# output_stage.net
KiCad netlist of a schematic drawn in Altium Designer
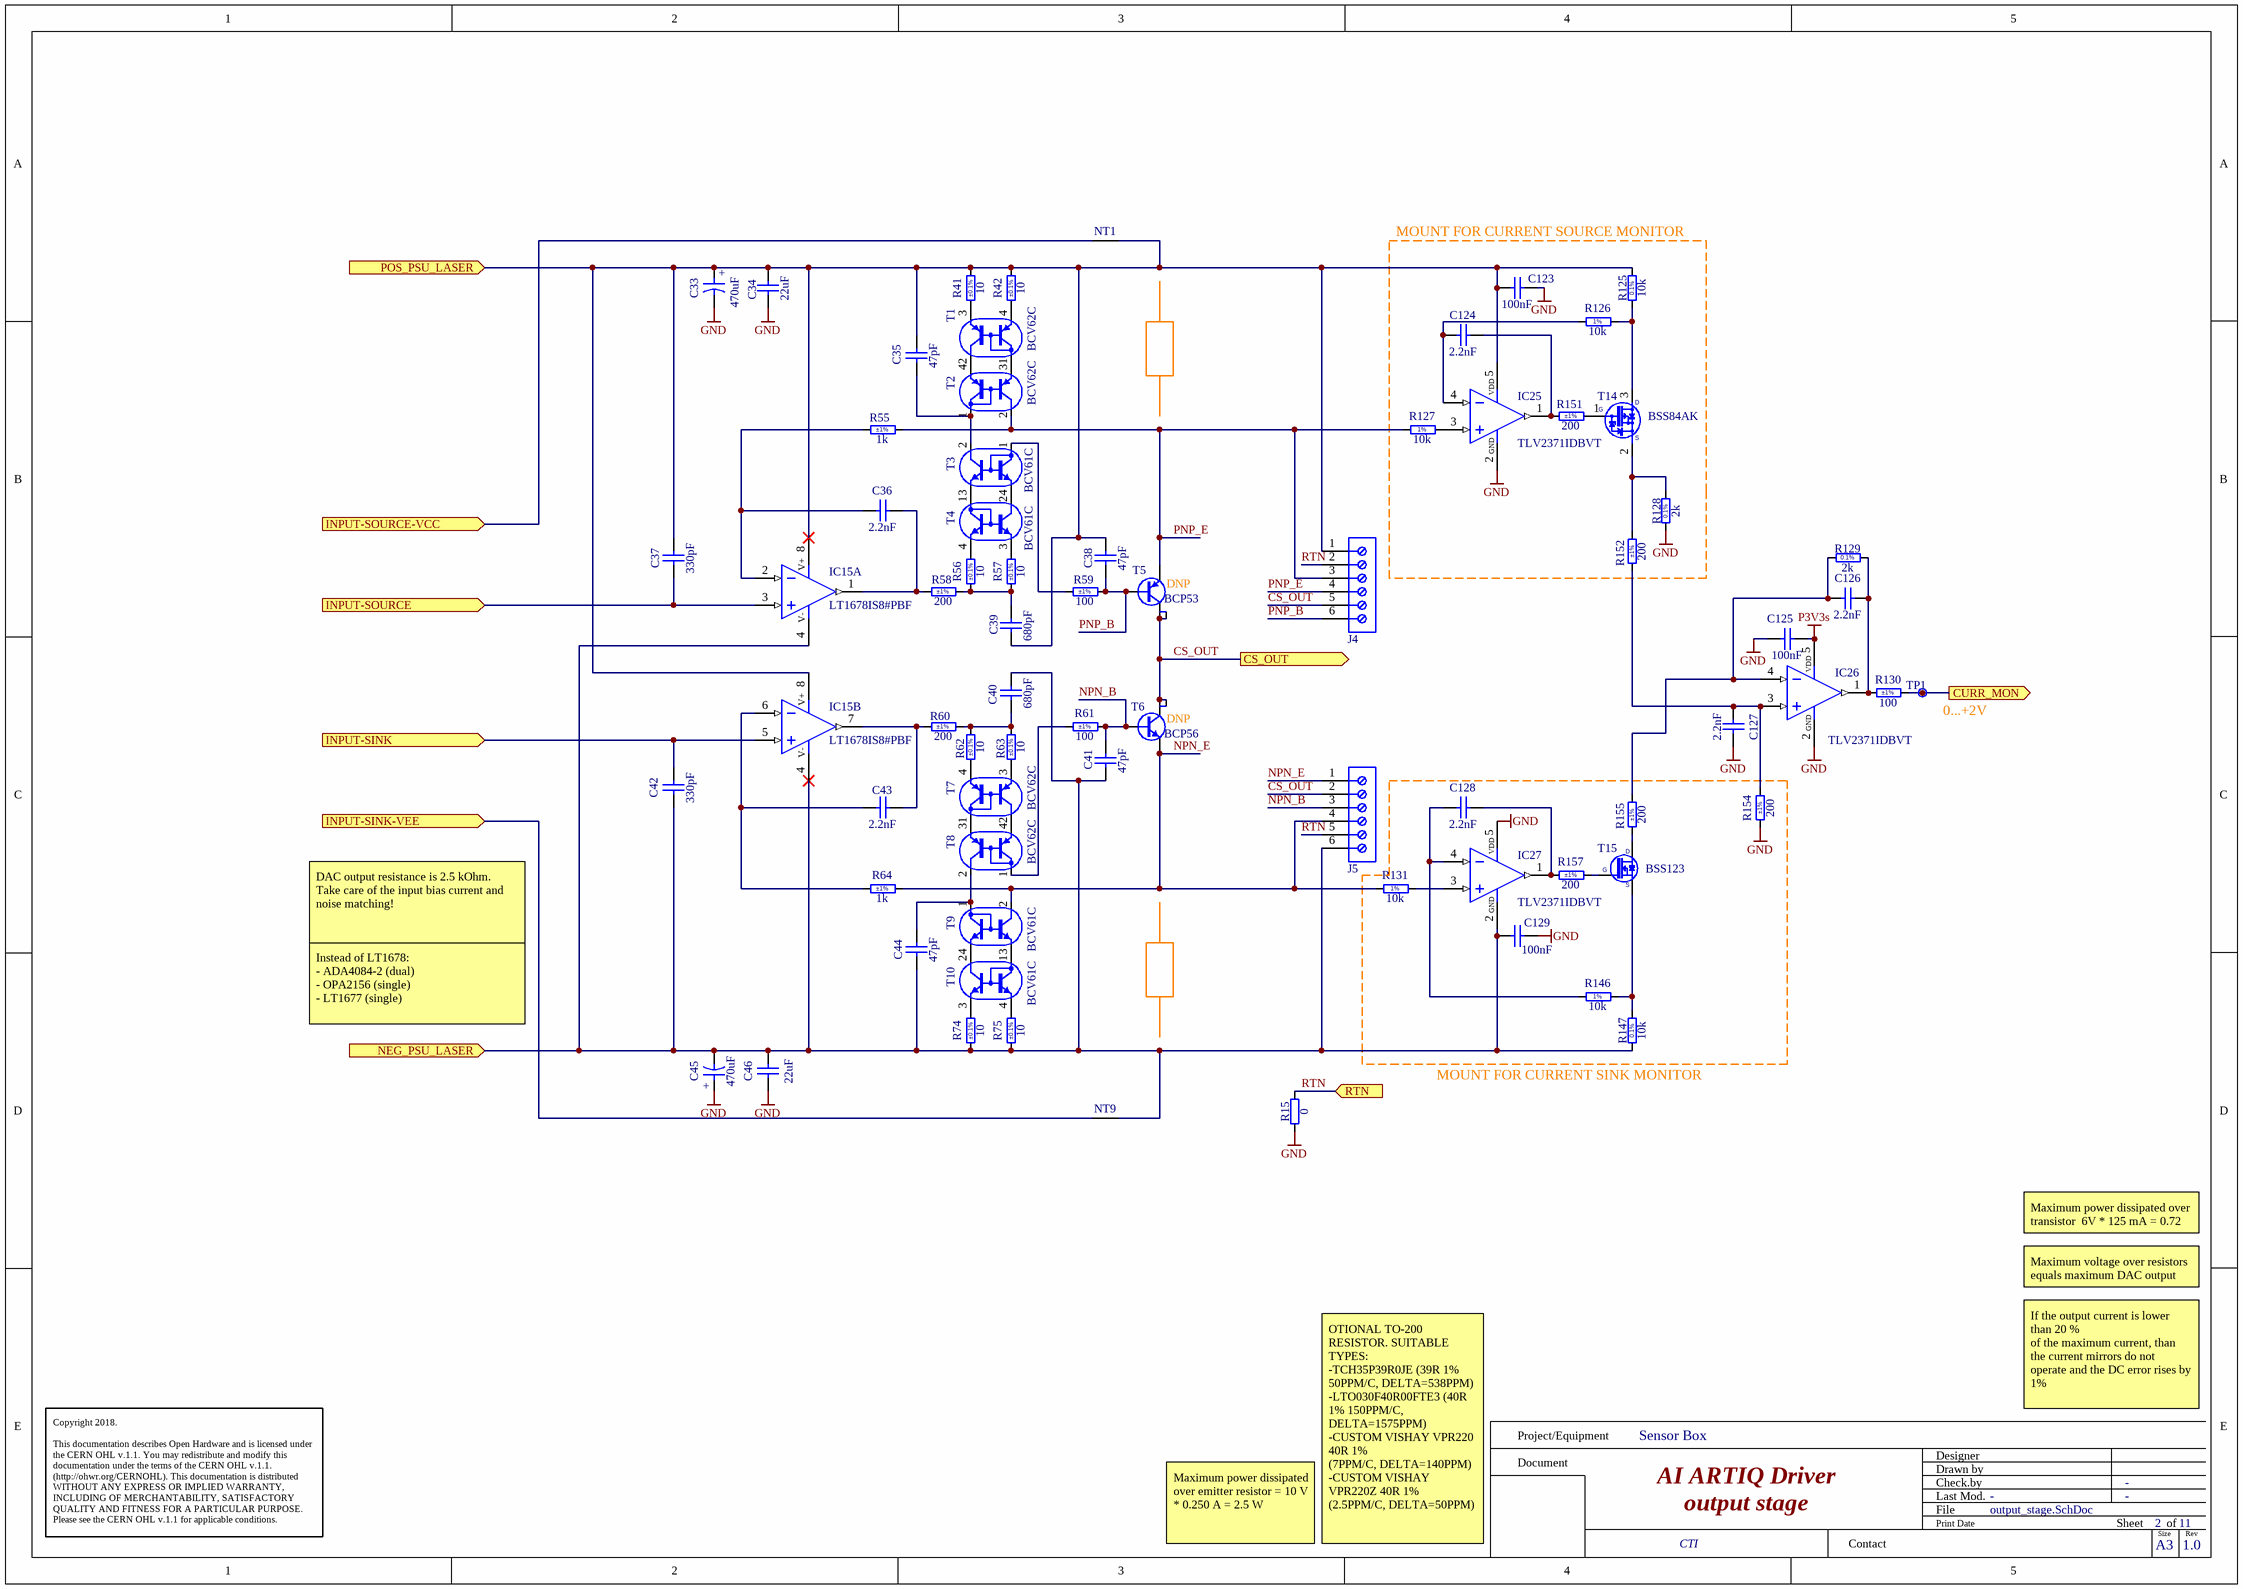
[diagram p0: output_stage.SchDoc]

(export (version "E")
  (design (tool "Eeschema 10.0.6"))
  (components
    (comp (ref "C33")
      (value "470uF")
      (footprint "CAPAE1030X1020N")
      (description "Polarised capacitor")
      (fields
        (field (name "PART NUMBER") "CAE1030-1020_470UF_25V_20%")
        (field (name "VOLTAGE") "25V")
        (field (name "AUTHOR") "CERN DEM JLC")
      )
      (libsource (lib "Capacitors") (part "Capacitor - polarized"))
    )
    (comp (ref "C34")
      (value "22uF")
      (footprint "CAPC3225X140N")
      (description "Non-polarised capacitor")
      (fields
        (field (name "PART NUMBER") "CC1210_22UF_25V_20%_X7R")
        (field (name "VOLTAGE") "25V")
        (field (name "AUTHOR") "CERN DEM JLC")
      )
      (libsource (lib "Capacitors") (part "Capacitor - non polarized"))
    )
    (comp (ref "C35")
      (value "47pF")
      (footprint "CAPC1608X87N")
      (description "Non-polarised capacitor")
      (fields
        (field (name "PART NUMBER") "CC0603_47PF_50V_5%_NP0")
        (field (name "VOLTAGE") "50V")
        (field (name "AUTHOR") "CERN DEM JLC")
      )
      (libsource (lib "Capacitors") (part "Capacitor - non polarized"))
    )
    (comp (ref "C36")
      (value "2.2nF")
      (footprint "CAPC1608X87N")
      (description "Non-polarised capacitor")
      (fields
        (field (name "PART NUMBER") "CC0603_2.2NF_50V_5%_C0G")
        (field (name "VOLTAGE") "50V")
        (field (name "AUTHOR") "CERN DEM JMW")
      )
      (libsource (lib "Capacitors") (part "Capacitor - non polarized"))
    )
    (comp (ref "C37")
      (value "330pF")
      (footprint "CAPC1608X90N")
      (description "Non-polarised capacitor")
      (fields
        (field (name "PART NUMBER") "CC0603_330PF_50V_5%_C0G_MURATA_GCM1885C1H331JA16D")
        (field (name "VOLTAGE") "50V")
        (field (name "AUTHOR") "CERN DEM JLC")
      )
      (libsource (lib "Capacitors") (part "Capacitor - non polarized"))
    )
    (comp (ref "C38")
      (value "47pF")
      (footprint "CAPC1608X87N")
      (description "Non-polarised capacitor")
      (fields
        (field (name "PART NUMBER") "CC0603_47PF_50V_5%_NP0")
        (field (name "VOLTAGE") "50V")
        (field (name "AUTHOR") "CERN DEM JLC")
      )
      (libsource (lib "Capacitors") (part "Capacitor - non polarized"))
    )
    (comp (ref "C39")
      (value "680pF")
      (footprint "CAPC1608X87N")
      (description "Non-polarised capacitor")
      (fields
        (field (name "PART NUMBER") "CC0603_680PF_50V_5%_NP0")
        (field (name "VOLTAGE") "50V")
        (field (name "AUTHOR") "CERN DEM JLC")
      )
      (libsource (lib "Capacitors") (part "Capacitor - non polarized"))
    )
    (comp (ref "C40")
      (value "680pF")
      (footprint "CAPC1608X87N")
      (description "Non-polarised capacitor")
      (fields
        (field (name "PART NUMBER") "CC0603_680PF_50V_5%_NP0")
        (field (name "VOLTAGE") "50V")
        (field (name "AUTHOR") "CERN DEM JLC")
      )
      (libsource (lib "Capacitors") (part "Capacitor - non polarized"))
    )
    (comp (ref "C41")
      (value "47pF")
      (footprint "CAPC1608X87N")
      (description "Non-polarised capacitor")
      (fields
        (field (name "PART NUMBER") "CC0603_47PF_50V_5%_NP0")
        (field (name "VOLTAGE") "50V")
        (field (name "AUTHOR") "CERN DEM JLC")
      )
      (libsource (lib "Capacitors") (part "Capacitor - non polarized"))
    )
    (comp (ref "C42")
      (value "330pF")
      (footprint "CAPC1608X90N")
      (description "Non-polarised capacitor")
      (fields
        (field (name "PART NUMBER") "CC0603_330PF_50V_5%_C0G_MURATA_GCM1885C1H331JA16D")
        (field (name "VOLTAGE") "50V")
        (field (name "AUTHOR") "CERN DEM JLC")
      )
      (libsource (lib "Capacitors") (part "Capacitor - non polarized"))
    )
    (comp (ref "C43")
      (value "2.2nF")
      (footprint "CAPC1608X87N")
      (description "Non-polarised capacitor")
      (fields
        (field (name "PART NUMBER") "CC0603_2.2NF_50V_5%_C0G")
        (field (name "VOLTAGE") "50V")
        (field (name "AUTHOR") "CERN DEM JMW")
      )
      (libsource (lib "Capacitors") (part "Capacitor - non polarized"))
    )
    (comp (ref "C44")
      (value "47pF")
      (footprint "CAPC1608X87N")
      (description "Non-polarised capacitor")
      (fields
        (field (name "PART NUMBER") "CC0603_47PF_50V_5%_NP0")
        (field (name "VOLTAGE") "50V")
        (field (name "AUTHOR") "CERN DEM JLC")
      )
      (libsource (lib "Capacitors") (part "Capacitor - non polarized"))
    )
    (comp (ref "C45")
      (value "470uF")
      (footprint "CAPAE1030X1020N")
      (description "Polarised capacitor")
      (fields
        (field (name "PART NUMBER") "CAE1030-1020_470UF_25V_20%")
        (field (name "VOLTAGE") "25V")
        (field (name "AUTHOR") "CERN DEM JLC")
      )
      (libsource (lib "Capacitors") (part "Capacitor - polarized"))
    )
    (comp (ref "C46")
      (value "22uF")
      (footprint "CAPC3225X140N")
      (description "Non-polarised capacitor")
      (fields
        (field (name "PART NUMBER") "CC1210_22UF_25V_20%_X7R")
        (field (name "VOLTAGE") "25V")
        (field (name "AUTHOR") "CERN DEM JLC")
      )
      (libsource (lib "Capacitors") (part "Capacitor - non polarized"))
    )
    (comp (ref "C123")
      (value "100nF")
      (footprint "CAPC1608X87N")
      (description "Non-polarised capacitor")
      (fields
        (field (name "PART NUMBER") "CC0603_100NF_50V_10%_X7R")
        (field (name "VOLTAGE") "50V")
        (field (name "AUTHOR") "CERN DEM JLC")
      )
      (libsource (lib "Capacitors") (part "Capacitor - non polarized"))
    )
    (comp (ref "C124")
      (value "2.2nF")
      (footprint "CAPC1608X87N")
      (description "Non-polarised capacitor")
      (fields
        (field (name "PART NUMBER") "CC0603_2.2NF_50V_5%_C0G")
        (field (name "VOLTAGE") "50V")
        (field (name "AUTHOR") "CERN DEM JMW")
      )
      (libsource (lib "Capacitors") (part "Capacitor - non polarized"))
    )
    (comp (ref "C125")
      (value "100nF")
      (footprint "CAPC1608X87N")
      (description "Non-polarised capacitor")
      (fields
        (field (name "PART NUMBER") "CC0603_100NF_50V_10%_X7R")
        (field (name "VOLTAGE") "50V")
        (field (name "AUTHOR") "CERN DEM JLC")
      )
      (libsource (lib "Capacitors") (part "Capacitor - non polarized"))
    )
    (comp (ref "C126")
      (value "2.2nF")
      (footprint "CAPC1608X87N")
      (description "Non-polarised capacitor")
      (fields
        (field (name "PART NUMBER") "CC0603_2.2NF_50V_5%_C0G")
        (field (name "VOLTAGE") "50V")
        (field (name "AUTHOR") "CERN DEM JMW")
      )
      (libsource (lib "Capacitors") (part "Capacitor - non polarized"))
    )
    (comp (ref "C127")
      (value "2.2nF")
      (footprint "CAPC1608X87N")
      (description "Non-polarised capacitor")
      (fields
        (field (name "PART NUMBER") "CC0603_2.2NF_50V_5%_C0G")
        (field (name "VOLTAGE") "50V")
        (field (name "AUTHOR") "CERN DEM JMW")
      )
      (libsource (lib "Capacitors") (part "Capacitor - non polarized"))
    )
    (comp (ref "C128")
      (value "2.2nF")
      (footprint "CAPC1608X87N")
      (description "Non-polarised capacitor")
      (fields
        (field (name "PART NUMBER") "CC0603_2.2NF_50V_5%_C0G")
        (field (name "VOLTAGE") "50V")
        (field (name "AUTHOR") "CERN DEM JMW")
      )
      (libsource (lib "Capacitors") (part "Capacitor - non polarized"))
    )
    (comp (ref "C129")
      (value "100nF")
      (footprint "CAPC1608X87N")
      (description "Non-polarised capacitor")
      (fields
        (field (name "PART NUMBER") "CC0603_100NF_50V_10%_X7R")
        (field (name "VOLTAGE") "50V")
        (field (name "AUTHOR") "CERN DEM JLC")
      )
      (libsource (lib "Capacitors") (part "Capacitor - non polarized"))
    )
    (comp (ref "IC15")
      (value "LT1678IS8#PBF")
      (footprint "SOIC127P600X175-8N")
      (description "Dual Operational Amplifier")
      (fields (field (name "MANUFACTURER") "LINEAR TECHNOLOGY") (field (name "AUTHOR") "CERN DEM JLC"))
      (libsource (lib "ICs And Semiconductors") (part "Operational Amplifier x2 Type1"))
    )
    (comp (ref "IC25")
      (value "TLV2371IDBVT")
      (footprint "SOT95P280X145-5N")
      (description "500uA, 3MHz Rail-to-Rail Input/Output Operational Amplifier With Shutdown")
      (fields (field (name "MANUFACTURER") "TEXAS INSTRUMENTS") (field (name "AUTHOR") "CERN DEM JLC"))
      (libsource (lib "ICs And Semiconductors") (part "TLV2371IDBVT"))
    )
    (comp (ref "IC26")
      (value "TLV2371IDBVT")
      (footprint "SOT95P280X145-5N")
      (description "500uA, 3MHz Rail-to-Rail Input/Output Operational Amplifier With Shutdown")
      (fields (field (name "MANUFACTURER") "TEXAS INSTRUMENTS") (field (name "AUTHOR") "CERN DEM JLC"))
      (libsource (lib "ICs And Semiconductors") (part "TLV2371IDBVT"))
    )
    (comp (ref "IC27")
      (value "TLV2371IDBVT")
      (footprint "SOT95P280X145-5N")
      (description "500uA, 3MHz Rail-to-Rail Input/Output Operational Amplifier With Shutdown")
      (fields (field (name "MANUFACTURER") "TEXAS INSTRUMENTS") (field (name "AUTHOR") "CERN DEM JLC"))
      (libsource (lib "ICs And Semiconductors") (part "TLV2371IDBVT"))
    )
    (comp (ref "J4")
      (value "691210910006")
      (footprint "691210910006")
      (description "WR-TBL Series 2109 Horizontal Entry, Through Hole, pitch 2.54mm, 6p")
      (fields (field (name "MANUFACTURER") "Wurth Elektronik"))
      (libsource (lib "Altium_WR-TBL (rev22a)") (part "691210910006"))
    )
    (comp (ref "J5")
      (value "691210910006")
      (footprint "691210910006")
      (description "WR-TBL Series 2109 Horizontal Entry, Through Hole, pitch 2.54mm, 6p")
      (fields (field (name "MANUFACTURER") "Wurth Elektronik"))
      (libsource (lib "Altium_WR-TBL (rev22a)") (part "691210910006"))
    )
    (comp (ref "NT1")
      (value "Net Tie")
      (footprint "Net Tie")
      (fields (field (name "AUTHOR") "CERN DEM JLC"))
      (libsource (lib "Eletro-mechanical") (part "Net Tie"))
    )
    (comp (ref "NT9")
      (value "Net Tie")
      (footprint "Net Tie")
      (fields (field (name "AUTHOR") "CERN DEM JLC"))
      (libsource (lib "Eletro-mechanical") (part "Net Tie"))
    )
    (comp (ref "R15")
      (value "0")
      (footprint "RESC2012X60N")
      (description "Resistor")
      (fields
        (field (name "PART NUMBER") "R0805_0R_JUMPER")
        (field (name "MANUFACTURER") "GENERIC")
        (field (name "AUTHOR") "CERN DEM JLC")
      )
      (libsource (lib "Resistors") (part "Resistor"))
    )
    (comp (ref "R41")
      (value "10")
      (footprint "RESC1608X55N")
      (description "Resistor - 0.1%")
      (fields
        (field (name "TOLERANCE") "±0.1%")
        (field (name "PART NUMBER") "R0603_10R_0.1%_0.063W_25PPM")
        (field (name "POWER") "0.063W")
        (field (name "AUTHOR") "CERN DEM JLC")
      )
      (libsource (lib "") (part "Resistor - 0.1%_1"))
    )
    (comp (ref "R42")
      (value "10")
      (footprint "RESC1608X55N")
      (description "Resistor - 0.1%")
      (fields
        (field (name "TOLERANCE") "±0.1%")
        (field (name "PART NUMBER") "R0603_10R_0.1%_0.063W_25PPM")
        (field (name "POWER") "0.063W")
        (field (name "AUTHOR") "CERN DEM JLC")
      )
      (libsource (lib "") (part "Resistor - 0.1%_1"))
    )
    (comp (ref "R55")
      (value "1k")
      (footprint "RESC1608X55N")
      (description "Resistor - 1%")
      (fields
        (field (name "TOLERANCE") "±1%")
        (field (name "PART NUMBER") "R0603_1K_1%_0.1W_100PPM")
        (field (name "POWER") "0.1W")
        (field (name "AUTHOR") "CERN DEM JLC")
      )
      (libsource (lib "Resistors") (part "Resistor - 1%"))
    )
    (comp (ref "R56")
      (value "10")
      (footprint "RESC1608X55N")
      (description "Resistor - 0.1%")
      (fields
        (field (name "TOLERANCE") "±0.1%")
        (field (name "PART NUMBER") "R0603_10R_0.1%_0.063W_25PPM")
        (field (name "POWER") "0.063W")
        (field (name "AUTHOR") "CERN DEM JLC")
      )
      (libsource (lib "") (part "Resistor - 0.1%_1"))
    )
    (comp (ref "R57")
      (value "10")
      (footprint "RESC1608X55N")
      (description "Resistor - 0.1%")
      (fields
        (field (name "TOLERANCE") "±0.1%")
        (field (name "PART NUMBER") "R0603_10R_0.1%_0.063W_25PPM")
        (field (name "POWER") "0.063W")
        (field (name "AUTHOR") "CERN DEM JLC")
      )
      (libsource (lib "") (part "Resistor - 0.1%_1"))
    )
    (comp (ref "R58")
      (value "200")
      (footprint "RESC1608X55N")
      (description "Resistor - 1%")
      (fields
        (field (name "TOLERANCE") "±1%")
        (field (name "PART NUMBER") "R0603_200R_1%_0.1W_100PPM")
        (field (name "POWER") "0.1W")
        (field (name "AUTHOR") "CERN DEM JLC")
      )
      (libsource (lib "Resistors") (part "Resistor - 1%"))
    )
    (comp (ref "R59")
      (value "100")
      (footprint "RESC1608X55N")
      (description "Resistor - 1%")
      (fields
        (field (name "TOLERANCE") "±1%")
        (field (name "PART NUMBER") "R0603_100R_1%_0.1W_100PPM")
        (field (name "POWER") "0.1W")
        (field (name "AUTHOR") "CERN DEM JLC")
      )
      (libsource (lib "Resistors") (part "Resistor - 1%"))
    )
    (comp (ref "R60")
      (value "200")
      (footprint "RESC1608X55N")
      (description "Resistor - 1%")
      (fields
        (field (name "TOLERANCE") "±1%")
        (field (name "PART NUMBER") "R0603_200R_1%_0.1W_100PPM")
        (field (name "POWER") "0.1W")
        (field (name "AUTHOR") "CERN DEM JLC")
      )
      (libsource (lib "Resistors") (part "Resistor - 1%"))
    )
    (comp (ref "R61")
      (value "100")
      (footprint "RESC1608X55N")
      (description "Resistor - 1%")
      (fields
        (field (name "TOLERANCE") "±1%")
        (field (name "PART NUMBER") "R0603_100R_1%_0.1W_100PPM")
        (field (name "POWER") "0.1W")
        (field (name "AUTHOR") "CERN DEM JLC")
      )
      (libsource (lib "Resistors") (part "Resistor - 1%"))
    )
    (comp (ref "R62")
      (value "10")
      (footprint "RESC1608X55N")
      (description "Resistor - 0.1%")
      (fields
        (field (name "TOLERANCE") "±0.1%")
        (field (name "PART NUMBER") "R0603_10R_0.1%_0.063W_25PPM")
        (field (name "POWER") "0.063W")
        (field (name "AUTHOR") "CERN DEM JLC")
      )
      (libsource (lib "") (part "Resistor - 0.1%_1"))
    )
    (comp (ref "R63")
      (value "10")
      (footprint "RESC1608X55N")
      (description "Resistor - 0.1%")
      (fields
        (field (name "TOLERANCE") "±0.1%")
        (field (name "PART NUMBER") "R0603_10R_0.1%_0.063W_25PPM")
        (field (name "POWER") "0.063W")
        (field (name "AUTHOR") "CERN DEM JLC")
      )
      (libsource (lib "") (part "Resistor - 0.1%_1"))
    )
    (comp (ref "R64")
      (value "1k")
      (footprint "RESC1608X55N")
      (description "Resistor - 1%")
      (fields
        (field (name "TOLERANCE") "±1%")
        (field (name "PART NUMBER") "R0603_1K_1%_0.1W_100PPM")
        (field (name "POWER") "0.1W")
        (field (name "AUTHOR") "CERN DEM JLC")
      )
      (libsource (lib "Resistors") (part "Resistor - 1%"))
    )
    (comp (ref "R74")
      (value "10")
      (footprint "RESC1608X55N")
      (description "Resistor - 0.1%")
      (fields
        (field (name "TOLERANCE") "±0.1%")
        (field (name "PART NUMBER") "R0603_10R_0.1%_0.063W_25PPM")
        (field (name "POWER") "0.063W")
        (field (name "AUTHOR") "CERN DEM JLC")
      )
      (libsource (lib "") (part "Resistor - 0.1%_1"))
    )
    (comp (ref "R75")
      (value "10")
      (footprint "RESC1608X55N")
      (description "Resistor - 0.1%")
      (fields
        (field (name "TOLERANCE") "±0.1%")
        (field (name "PART NUMBER") "R0603_10R_0.1%_0.063W_25PPM")
        (field (name "POWER") "0.063W")
        (field (name "AUTHOR") "CERN DEM JLC")
      )
      (libsource (lib "") (part "Resistor - 0.1%_1"))
    )
    (comp (ref "R125")
      (value "10k")
      (footprint "RESC1608X64N")
      (description "Resistor - 0.1%")
      (fields
        (field (name "PART NUMBER") "R0603_10K_0.1%_0.1W_25PPM")
        (field (name "POWER") "0.1W")
        (field (name "AUTHOR") "CERN DEM JMW")
      )
      (libsource (lib "Resistors") (part "Resistor - 0.1%"))
    )
    (comp (ref "R126")
      (value "10k")
      (footprint "RESC1608X55N")
      (description "Resistor - 1%")
      (fields
        (field (name "PART NUMBER") "R0603_10K_1%_0.1W_100PPM")
        (field (name "POWER") "0.1W")
        (field (name "AUTHOR") "CERN DEM JLC")
      )
      (libsource (lib "Resistors") (part "Resistor - 1%"))
    )
    (comp (ref "R127")
      (value "10k")
      (footprint "RESC1608X55N")
      (description "Resistor - 1%")
      (fields
        (field (name "PART NUMBER") "R0603_10K_1%_0.1W_100PPM")
        (field (name "POWER") "0.1W")
        (field (name "AUTHOR") "CERN DEM JLC")
      )
      (libsource (lib "Resistors") (part "Resistor - 1%"))
    )
    (comp (ref "R128")
      (value "2k")
      (footprint "RESC1608X55N")
      (description "Resistor - 0.1%")
      (fields
        (field (name "PART NUMBER") "R0603_2K_0.1%_0.063W_10PPM")
        (field (name "POWER") "0.063W")
        (field (name "AUTHOR") "CERN DEM JLC")
      )
      (libsource (lib "Resistors") (part "Resistor - 0.1%"))
    )
    (comp (ref "R129")
      (value "2k")
      (footprint "RESC1608X55N")
      (description "Resistor - 0.1%")
      (fields
        (field (name "PART NUMBER") "R0603_2K_0.1%_0.063W_10PPM")
        (field (name "POWER") "0.063W")
        (field (name "AUTHOR") "CERN DEM JLC")
      )
      (libsource (lib "Resistors") (part "Resistor - 0.1%"))
    )
    (comp (ref "R130")
      (value "100")
      (footprint "RESC1608X55N")
      (description "Resistor - 1%")
      (fields
        (field (name "TOLERANCE") "±1%")
        (field (name "PART NUMBER") "R0603_100R_1%_0.1W_100PPM")
        (field (name "POWER") "0.1W")
        (field (name "AUTHOR") "CERN DEM JLC")
      )
      (libsource (lib "Resistors") (part "Resistor - 1%"))
    )
    (comp (ref "R131")
      (value "10k")
      (footprint "RESC1608X55N")
      (description "Resistor - 1%")
      (fields
        (field (name "PART NUMBER") "R0603_10K_1%_0.1W_100PPM")
        (field (name "POWER") "0.1W")
        (field (name "AUTHOR") "CERN DEM JLC")
      )
      (libsource (lib "Resistors") (part "Resistor - 1%"))
    )
    (comp (ref "R146")
      (value "10k")
      (footprint "RESC1608X55N")
      (description "Resistor - 1%")
      (fields
        (field (name "PART NUMBER") "R0603_10K_1%_0.1W_100PPM")
        (field (name "POWER") "0.1W")
        (field (name "AUTHOR") "CERN DEM JLC")
      )
      (libsource (lib "Resistors") (part "Resistor - 1%"))
    )
    (comp (ref "R147")
      (value "10k")
      (footprint "RESC1608X64N")
      (description "Resistor - 0.1%")
      (fields
        (field (name "PART NUMBER") "R0603_10K_0.1%_0.1W_25PPM")
        (field (name "POWER") "0.1W")
        (field (name "AUTHOR") "CERN DEM JMW")
      )
      (libsource (lib "Resistors") (part "Resistor - 0.1%"))
    )
    (comp (ref "R151")
      (value "200")
      (footprint "RESC1608X55N")
      (description "Resistor - 1%")
      (fields
        (field (name "TOLERANCE") "±1%")
        (field (name "PART NUMBER") "R0603_200R_1%_0.1W_100PPM")
        (field (name "POWER") "0.1W")
        (field (name "AUTHOR") "CERN DEM JLC")
      )
      (libsource (lib "Resistors") (part "Resistor - 1%"))
    )
    (comp (ref "R152")
      (value "200")
      (footprint "RESC1608X55N")
      (description "Resistor - 1%")
      (fields
        (field (name "TOLERANCE") "±1%")
        (field (name "PART NUMBER") "R0603_200R_1%_0.1W_100PPM")
        (field (name "POWER") "0.1W")
        (field (name "AUTHOR") "CERN DEM JLC")
      )
      (libsource (lib "Resistors") (part "Resistor - 1%"))
    )
    (comp (ref "R154")
      (value "200")
      (footprint "RESC1608X55N")
      (description "Resistor - 1%")
      (fields
        (field (name "TOLERANCE") "±1%")
        (field (name "PART NUMBER") "R0603_200R_1%_0.1W_100PPM")
        (field (name "POWER") "0.1W")
        (field (name "AUTHOR") "CERN DEM JLC")
      )
      (libsource (lib "Resistors") (part "Resistor - 1%"))
    )
    (comp (ref "R155")
      (value "200")
      (footprint "RESC1608X55N")
      (description "Resistor - 1%")
      (fields
        (field (name "TOLERANCE") "±1%")
        (field (name "PART NUMBER") "R0603_200R_1%_0.1W_100PPM")
        (field (name "POWER") "0.1W")
        (field (name "AUTHOR") "CERN DEM JLC")
      )
      (libsource (lib "Resistors") (part "Resistor - 1%"))
    )
    (comp (ref "R157")
      (value "200")
      (footprint "RESC1608X55N")
      (description "Resistor - 1%")
      (fields
        (field (name "TOLERANCE") "±1%")
        (field (name "PART NUMBER") "R0603_200R_1%_0.1W_100PPM")
        (field (name "POWER") "0.1W")
        (field (name "AUTHOR") "CERN DEM JLC")
      )
      (libsource (lib "Resistors") (part "Resistor - 1%"))
    )
    (comp (ref "T1")
      (value "BCV62C")
      (footprint "SOT143N")
      (description "Double PNP Transistor")
      (fields (field (name "MANUFACTURER") "NXP SEMICONDUCTORS") (field (name "AUTHOR") "CERN DEM JLC"))
      (libsource (lib "ICs And Semiconductors") (part "BCV62"))
    )
    (comp (ref "T2")
      (value "BCV62C")
      (footprint "SOT143N")
      (description "Double PNP Transistor")
      (fields (field (name "MANUFACTURER") "NXP SEMICONDUCTORS") (field (name "AUTHOR") "CERN DEM JLC"))
      (libsource (lib "") (part "BCV62_1"))
    )
    (comp (ref "T3")
      (value "BCV61C")
      (footprint "SOT143N")
      (description "Double NPN Transistor")
      (fields (field (name "MANUFACTURER") "NXP SEMICONDUCTORS") (field (name "AUTHOR") "CERN DEM JLC"))
      (libsource (lib "ICs And Semiconductors") (part "BCV61"))
    )
    (comp (ref "T4")
      (value "BCV61C")
      (footprint "SOT143N")
      (description "Double NPN Transistor")
      (fields (field (name "MANUFACTURER") "NXP SEMICONDUCTORS") (field (name "AUTHOR") "CERN DEM JLC"))
      (libsource (lib "") (part "BCV61_1"))
    )
    (comp (ref "T5")
      (value "BCP53")
      (footprint "SOT230P700X180-4N")
      (description "PNP Transistor")
      (fields (field (name "MANUFACTURER") "NXP SEMICONDUCTORS") (field (name "AUTHOR") "CERN DEM JLC"))
      (libsource (lib "ICs And Semiconductors") (part "PNP B1 C2 E3 C4"))
    )
    (comp (ref "T6")
      (value "BCP56")
      (footprint "SOT230P700X180-4N")
      (description "NPN Transistor")
      (fields (field (name "MANUFACTURER") "NXP SEMICONDUCTORS") (field (name "AUTHOR") "CERN DEM JLC"))
      (libsource (lib "ICs And Semiconductors") (part "NPN B1 C2 E3 C4"))
    )
    (comp (ref "T7")
      (value "BCV62C")
      (footprint "SOT143N")
      (description "Double PNP Transistor")
      (fields (field (name "MANUFACTURER") "NXP SEMICONDUCTORS") (field (name "AUTHOR") "CERN DEM JLC"))
      (libsource (lib "") (part "BCV62_1"))
    )
    (comp (ref "T8")
      (value "BCV62C")
      (footprint "SOT143N")
      (description "Double PNP Transistor")
      (fields (field (name "MANUFACTURER") "NXP SEMICONDUCTORS") (field (name "AUTHOR") "CERN DEM JLC"))
      (libsource (lib "ICs And Semiconductors") (part "BCV62"))
    )
    (comp (ref "T9")
      (value "BCV61C")
      (footprint "SOT143N")
      (description "Double NPN Transistor")
      (fields (field (name "MANUFACTURER") "NXP SEMICONDUCTORS") (field (name "AUTHOR") "CERN DEM JLC"))
      (libsource (lib "") (part "BCV61_1"))
    )
    (comp (ref "T10")
      (value "BCV61C")
      (footprint "SOT143N")
      (description "Double NPN Transistor")
      (fields (field (name "MANUFACTURER") "NXP SEMICONDUCTORS") (field (name "AUTHOR") "CERN DEM JLC"))
      (libsource (lib "ICs And Semiconductors") (part "BCV61"))
    )
    (comp (ref "T14")
      (value "BSS84AK")
      (footprint "SOT95P230X110-3N")
      (description "50V, 180mA P-Channel Trench MOSFET")
      (fields (field (name "MANUFACTURER") "NXP SEMICONDUCTORS") (field (name "AUTHOR") "CERN DEM JLC"))
      (libsource (lib "ICs And Semiconductors") (part "BSS84"))
    )
    (comp (ref "T15")
      (value "BSS123")
      (footprint "SOT95P240X130-3N")
      (description "N-CHANNEL MOSFET WITH DIODE")
      (fields (field (name "MANUFACTURER") "FAIRCHILD SEMICONDUCTOR") (field (name "AUTHOR") "CERN DEM JLC"))
      (libsource (lib "ICs And Semiconductors") (part "N-MOSFET-D 1G 2S 3D"))
    )
    (comp (ref "TP1")
      (value "Test Point")
      (footprint "TPS127")
      (fields (field (name "PART NUMBER") "SMD_PAD_1.27X1.27MM") (field (name "AUTHOR") "CERN DEM JLC"))
      (libsource (lib "Eletro-mechanical") (part "Test Point"))
    )
  )
  (nets
    (net (code "1") (name "/CS_OUT") (class "Default")
      (node (ref "J4") (pin "5") (pinfunction "5_5") (pintype "passive"))
      (node (ref "J5") (pin "2") (pinfunction "2_2") (pintype "passive"))
      (node (ref "T5") (pin "2") (pinfunction "C_2") (pintype "passive"))
      (node (ref "T5") (pin "4") (pinfunction "C_4") (pintype "passive"))
      (node (ref "T6") (pin "2") (pinfunction "C_2") (pintype "passive"))
      (node (ref "T6") (pin "4") (pinfunction "C_4") (pintype "passive"))
    )
    (net (code "2") (name "/CURR_MON") (class "Default")
      (node (ref "R130") (pin "2") (pinfunction "2_2") (pintype "passive"))
      (node (ref "TP1") (pin "1") (pinfunction "1_1") (pintype "bidirectional"))
    )
    (net (code "3") (name "/INPUT-SINK") (class "Default")
      (node (ref "C42") (pin "2") (pinfunction "2_2") (pintype "passive"))
      (node (ref "IC15") (pin "5") (pinfunction "IN+_5") (pintype "input"))
    )
    (net (code "4") (name "/INPUT-SINK-VEE") (class "Default")
      (node (ref "NT9") (pin "1") (pinfunction "1_1") (pintype "bidirectional"))
    )
    (net (code "5") (name "/INPUT-SOURCE") (class "Default")
      (node (ref "C37") (pin "1") (pinfunction "1_1") (pintype "passive"))
      (node (ref "IC15") (pin "3") (pinfunction "IN+_3") (pintype "input"))
    )
    (net (code "6") (name "/INPUT-SOURCE-VCC") (class "Default")
      (node (ref "NT1") (pin "1") (pinfunction "1_1") (pintype "bidirectional"))
    )
    (net (code "7") (name "/NEG_PSU_LASER") (class "Default")
      (node (ref "C129") (pin "2") (pinfunction "2_2") (pintype "passive"))
      (node (ref "C40") (pin "2") (pinfunction "2_2") (pintype "passive"))
      (node (ref "C41") (pin "1") (pinfunction "1_1") (pintype "passive"))
      (node (ref "C42") (pin "1") (pinfunction "1_1") (pintype "passive"))
      (node (ref "C44") (pin "1") (pinfunction "1_1") (pintype "passive"))
      (node (ref "C45") (pin "2") (pinfunction "2_2") (pintype "passive"))
      (node (ref "C46") (pin "1") (pinfunction "1_1") (pintype "passive"))
      (node (ref "IC15") (pin "4") (pinfunction "V-_4") (pintype "power_in"))
      (node (ref "IC27") (pin "2") (pinfunction "V-_2") (pintype "power_in"))
      (node (ref "J5") (pin "6") (pinfunction "6_6") (pintype "passive"))
      (node (ref "NT9") (pin "2") (pinfunction "2_2") (pintype "bidirectional"))
      (node (ref "R147") (pin "1") (pinfunction "1_1") (pintype "passive"))
      (node (ref "R74") (pin "1") (pinfunction "1_1") (pintype "passive"))
      (node (ref "R75") (pin "1") (pinfunction "1_1") (pintype "passive"))
    )
    (net (code "8") (name "/NPN_B") (class "Default")
      (node (ref "C41") (pin "2") (pinfunction "2_2") (pintype "passive"))
      (node (ref "J5") (pin "3") (pinfunction "3_3") (pintype "passive"))
      (node (ref "R61") (pin "2") (pinfunction "2_2") (pintype "passive"))
      (node (ref "T6") (pin "1") (pinfunction "B_1") (pintype "passive"))
    )
    (net (code "9") (name "/NPN_E") (class "Default")
      (node (ref "J5") (pin "1") (pinfunction "1_1") (pintype "passive"))
      (node (ref "J5") (pin "4") (pinfunction "4_4") (pintype "passive"))
      (node (ref "R131") (pin "1") (pinfunction "1_1") (pintype "passive"))
      (node (ref "R64") (pin "2") (pinfunction "2_2") (pintype "passive"))
      (node (ref "T6") (pin "3") (pinfunction "E_3") (pintype "passive"))
      (node (ref "T9") (pin "2") (pinfunction "C_2") (pintype "passive"))
    )
    (net (code "10") (name "/PNP_B") (class "Default")
      (node (ref "C38") (pin "1") (pinfunction "1_1") (pintype "passive"))
      (node (ref "J4") (pin "6") (pinfunction "6_6") (pintype "passive"))
      (node (ref "R59") (pin "2") (pinfunction "2_2") (pintype "passive"))
      (node (ref "T5") (pin "1") (pinfunction "B_1") (pintype "passive"))
    )
    (net (code "11") (name "/PNP_E") (class "Default")
      (node (ref "J4") (pin "3") (pinfunction "3_3") (pintype "passive"))
      (node (ref "J4") (pin "4") (pinfunction "4_4") (pintype "passive"))
      (node (ref "R127") (pin "1") (pinfunction "1_1") (pintype "passive"))
      (node (ref "R55") (pin "2") (pinfunction "2_2") (pintype "passive"))
      (node (ref "T2") (pin "2") (pinfunction "C_2") (pintype "passive"))
      (node (ref "T5") (pin "3") (pinfunction "E_3") (pintype "passive"))
    )
    (net (code "12") (name "/POS_PSU_LASER") (class "Default")
      (node (ref "C123") (pin "1") (pinfunction "1_1") (pintype "passive"))
      (node (ref "C33") (pin "1") (pinfunction "1_1") (pintype "passive"))
      (node (ref "C34") (pin "2") (pinfunction "2_2") (pintype "passive"))
      (node (ref "C35") (pin "2") (pinfunction "2_2") (pintype "passive"))
      (node (ref "C37") (pin "2") (pinfunction "2_2") (pintype "passive"))
      (node (ref "C38") (pin "2") (pinfunction "2_2") (pintype "passive"))
      (node (ref "C39") (pin "1") (pinfunction "1_1") (pintype "passive"))
      (node (ref "IC15") (pin "8") (pinfunction "V+_8") (pintype "power_in"))
      (node (ref "IC25") (pin "5") (pinfunction "V+_5") (pintype "power_in"))
      (node (ref "J4") (pin "1") (pinfunction "1_1") (pintype "passive"))
      (node (ref "NT1") (pin "2") (pinfunction "2_2") (pintype "bidirectional"))
      (node (ref "R125") (pin "2") (pinfunction "2_2") (pintype "passive"))
      (node (ref "R41") (pin "2") (pinfunction "2_2") (pintype "passive"))
      (node (ref "R42") (pin "2") (pinfunction "2_2") (pintype "passive"))
    )
    (net (code "13") (name "/RTN") (class "Default")
      (node (ref "J4") (pin "2") (pinfunction "2_2") (pintype "passive"))
      (node (ref "J5") (pin "5") (pinfunction "5_5") (pintype "passive"))
      (node (ref "R15") (pin "2") (pinfunction "2_2") (pintype "passive"))
    )
    (net (code "14") (name "GND") (class "Default")
      (node (ref "C123") (pin "2") (pinfunction "2_2") (pintype "passive"))
      (node (ref "C125") (pin "1") (pinfunction "1_1") (pintype "passive"))
      (node (ref "C127") (pin "2") (pinfunction "2_2") (pintype "passive"))
      (node (ref "C129") (pin "1") (pinfunction "1_1") (pintype "passive"))
      (node (ref "C33") (pin "2") (pinfunction "2_2") (pintype "passive"))
      (node (ref "C34") (pin "1") (pinfunction "1_1") (pintype "passive"))
      (node (ref "C45") (pin "1") (pinfunction "1_1") (pintype "passive"))
      (node (ref "C46") (pin "2") (pinfunction "2_2") (pintype "passive"))
      (node (ref "IC25") (pin "2") (pinfunction "V-_2") (pintype "power_in"))
      (node (ref "IC26") (pin "2") (pinfunction "V-_2") (pintype "power_in"))
      (node (ref "IC27") (pin "5") (pinfunction "V+_5") (pintype "power_in"))
      (node (ref "R128") (pin "1") (pinfunction "1_1") (pintype "passive"))
      (node (ref "R15") (pin "1") (pinfunction "1_1") (pintype "passive"))
      (node (ref "R154") (pin "1") (pinfunction "1_1") (pintype "passive"))
    )
    (net (code "15") (name "Net-(C35-Pad1)") (class "Default")
      (node (ref "C35") (pin "1") (pinfunction "1_1") (pintype "passive"))
      (node (ref "T2") (pin "1") (pinfunction "C_1") (pintype "passive"))
      (node (ref "T3") (pin "2") (pinfunction "C_2") (pintype "passive"))
    )
    (net (code "16") (name "Net-(C39-Pad2)") (class "Default")
      (node (ref "C39") (pin "2") (pinfunction "2_2") (pintype "passive"))
      (node (ref "R56") (pin "1") (pinfunction "1_1") (pintype "passive"))
      (node (ref "R57") (pin "1") (pinfunction "1_1") (pintype "passive"))
      (node (ref "R58") (pin "2") (pinfunction "2_2") (pintype "passive"))
    )
    (net (code "17") (name "Net-(C40-Pad1)") (class "Default")
      (node (ref "C40") (pin "1") (pinfunction "1_1") (pintype "passive"))
      (node (ref "R60") (pin "2") (pinfunction "2_2") (pintype "passive"))
      (node (ref "R62") (pin "2") (pinfunction "2_2") (pintype "passive"))
      (node (ref "R63") (pin "2") (pinfunction "2_2") (pintype "passive"))
    )
    (net (code "18") (name "Net-(C44-Pad2)") (class "Default")
      (node (ref "C44") (pin "2") (pinfunction "2_2") (pintype "passive"))
      (node (ref "T8") (pin "2") (pinfunction "C_2") (pintype "passive"))
      (node (ref "T9") (pin "1") (pinfunction "C_1") (pintype "passive"))
    )
    (net (code "19") (name "Net-(IC15A-IN-)") (class "Default")
      (node (ref "C36") (pin "1") (pinfunction "1_1") (pintype "passive"))
      (node (ref "IC15") (pin "2") (pinfunction "IN-_2") (pintype "input"))
      (node (ref "R55") (pin "1") (pinfunction "1_1") (pintype "passive"))
    )
    (net (code "20") (name "Net-(IC15A-OUT)") (class "Default")
      (node (ref "C36") (pin "2") (pinfunction "2_2") (pintype "passive"))
      (node (ref "IC15") (pin "1") (pinfunction "OUT_1") (pintype "output"))
      (node (ref "R58") (pin "1") (pinfunction "1_1") (pintype "passive"))
    )
    (net (code "21") (name "Net-(IC15B-IN-)") (class "Default")
      (node (ref "C43") (pin "1") (pinfunction "1_1") (pintype "passive"))
      (node (ref "IC15") (pin "6") (pinfunction "IN-_6") (pintype "input"))
      (node (ref "R64") (pin "1") (pinfunction "1_1") (pintype "passive"))
    )
    (net (code "22") (name "Net-(IC15B-OUT)") (class "Default")
      (node (ref "C43") (pin "2") (pinfunction "2_2") (pintype "passive"))
      (node (ref "IC15") (pin "7") (pinfunction "OUT_7") (pintype "output"))
      (node (ref "R60") (pin "1") (pinfunction "1_1") (pintype "passive"))
    )
    (net (code "23") (name "Net-(IC25-IN+)") (class "Default")
      (node (ref "IC25") (pin "3") (pinfunction "IN+_3") (pintype "input"))
      (node (ref "R127") (pin "2") (pinfunction "2_2") (pintype "passive"))
    )
    (net (code "24") (name "Net-(IC25-IN-)") (class "Default")
      (node (ref "C124") (pin "1") (pinfunction "1_1") (pintype "passive"))
      (node (ref "IC25") (pin "4") (pinfunction "IN-_4") (pintype "input"))
      (node (ref "R126") (pin "1") (pinfunction "1_1") (pintype "passive"))
    )
    (net (code "25") (name "Net-(IC25-OUT)") (class "Default")
      (node (ref "C124") (pin "2") (pinfunction "2_2") (pintype "passive"))
      (node (ref "IC25") (pin "1") (pinfunction "OUT_1") (pintype "output"))
      (node (ref "R151") (pin "1") (pinfunction "1_1") (pintype "passive"))
    )
    (net (code "26") (name "Net-(IC26-IN+)") (class "Default")
      (node (ref "C127") (pin "1") (pinfunction "1_1") (pintype "passive"))
      (node (ref "IC26") (pin "3") (pinfunction "IN+_3") (pintype "input"))
      (node (ref "R152") (pin "1") (pinfunction "1_1") (pintype "passive"))
      (node (ref "R154") (pin "2") (pinfunction "2_2") (pintype "passive"))
    )
    (net (code "27") (name "Net-(IC26-IN-)") (class "Default")
      (node (ref "C126") (pin "1") (pinfunction "1_1") (pintype "passive"))
      (node (ref "IC26") (pin "4") (pinfunction "IN-_4") (pintype "input"))
      (node (ref "R129") (pin "1") (pinfunction "1_1") (pintype "passive"))
      (node (ref "R155") (pin "2") (pinfunction "2_2") (pintype "passive"))
    )
    (net (code "28") (name "Net-(IC26-OUT)") (class "Default")
      (node (ref "C126") (pin "2") (pinfunction "2_2") (pintype "passive"))
      (node (ref "IC26") (pin "1") (pinfunction "OUT_1") (pintype "output"))
      (node (ref "R129") (pin "2") (pinfunction "2_2") (pintype "passive"))
      (node (ref "R130") (pin "1") (pinfunction "1_1") (pintype "passive"))
    )
    (net (code "29") (name "Net-(IC27-IN+)") (class "Default")
      (node (ref "IC27") (pin "3") (pinfunction "IN+_3") (pintype "input"))
      (node (ref "R131") (pin "2") (pinfunction "2_2") (pintype "passive"))
    )
    (net (code "30") (name "Net-(IC27-IN-)") (class "Default")
      (node (ref "C128") (pin "1") (pinfunction "1_1") (pintype "passive"))
      (node (ref "IC27") (pin "4") (pinfunction "IN-_4") (pintype "input"))
      (node (ref "R146") (pin "1") (pinfunction "1_1") (pintype "passive"))
    )
    (net (code "31") (name "Net-(IC27-OUT)") (class "Default")
      (node (ref "C128") (pin "2") (pinfunction "2_2") (pintype "passive"))
      (node (ref "IC27") (pin "1") (pinfunction "OUT_1") (pintype "output"))
      (node (ref "R157") (pin "1") (pinfunction "1_1") (pintype "passive"))
    )
    (net (code "32") (name "Net-(R41-Pad1)") (class "Default")
      (node (ref "R41") (pin "1") (pinfunction "1_1") (pintype "passive"))
      (node (ref "T1") (pin "3") (pinfunction "E_3") (pintype "passive"))
    )
    (net (code "33") (name "Net-(R42-Pad1)") (class "Default")
      (node (ref "R42") (pin "1") (pinfunction "1_1") (pintype "passive"))
      (node (ref "T1") (pin "4") (pinfunction "E_4") (pintype "passive"))
    )
    (net (code "34") (name "Net-(R56-Pad2)") (class "Default")
      (node (ref "R56") (pin "2") (pinfunction "2_2") (pintype "passive"))
      (node (ref "T4") (pin "4") (pinfunction "E_4") (pintype "passive"))
    )
    (net (code "35") (name "Net-(R57-Pad2)") (class "Default")
      (node (ref "R57") (pin "2") (pinfunction "2_2") (pintype "passive"))
      (node (ref "T4") (pin "3") (pinfunction "E_3") (pintype "passive"))
    )
    (net (code "36") (name "Net-(R59-Pad1)") (class "Default")
      (node (ref "R59") (pin "1") (pinfunction "1_1") (pintype "passive"))
      (node (ref "T3") (pin "1") (pinfunction "C_1") (pintype "passive"))
    )
    (net (code "37") (name "Net-(R61-Pad1)") (class "Default")
      (node (ref "R61") (pin "1") (pinfunction "1_1") (pintype "passive"))
      (node (ref "T8") (pin "1") (pinfunction "C_1") (pintype "passive"))
    )
    (net (code "38") (name "Net-(R62-Pad1)") (class "Default")
      (node (ref "R62") (pin "1") (pinfunction "1_1") (pintype "passive"))
      (node (ref "T7") (pin "4") (pinfunction "E_4") (pintype "passive"))
    )
    (net (code "39") (name "Net-(R63-Pad1)") (class "Default")
      (node (ref "R63") (pin "1") (pinfunction "1_1") (pintype "passive"))
      (node (ref "T7") (pin "3") (pinfunction "E_3") (pintype "passive"))
    )
    (net (code "40") (name "Net-(R74-Pad2)") (class "Default")
      (node (ref "R74") (pin "2") (pinfunction "2_2") (pintype "passive"))
      (node (ref "T10") (pin "3") (pinfunction "E_3") (pintype "passive"))
    )
    (net (code "41") (name "Net-(R75-Pad2)") (class "Default")
      (node (ref "R75") (pin "2") (pinfunction "2_2") (pintype "passive"))
      (node (ref "T10") (pin "4") (pinfunction "E_4") (pintype "passive"))
    )
    (net (code "42") (name "Net-(T1-C-Pad1)") (class "Default")
      (node (ref "T1") (pin "1") (pinfunction "C_1") (pintype "passive"))
      (node (ref "T2") (pin "3") (pinfunction "E_3") (pintype "passive"))
    )
    (net (code "43") (name "Net-(T1-C-Pad2)") (class "Default")
      (node (ref "T1") (pin "2") (pinfunction "C_2") (pintype "passive"))
      (node (ref "T2") (pin "4") (pinfunction "E_4") (pintype "passive"))
    )
    (net (code "44") (name "Net-(T3-E-Pad3)") (class "Default")
      (node (ref "T3") (pin "3") (pinfunction "E_3") (pintype "passive"))
      (node (ref "T4") (pin "1") (pinfunction "C_1") (pintype "passive"))
    )
    (net (code "45") (name "Net-(T3-E-Pad4)") (class "Default")
      (node (ref "T3") (pin "4") (pinfunction "E_4") (pintype "passive"))
      (node (ref "T4") (pin "2") (pinfunction "C_2") (pintype "passive"))
    )
    (net (code "46") (name "Net-(T7-C-Pad1)") (class "Default")
      (node (ref "T7") (pin "1") (pinfunction "C_1") (pintype "passive"))
      (node (ref "T8") (pin "3") (pinfunction "E_3") (pintype "passive"))
    )
    (net (code "47") (name "Net-(T7-C-Pad2)") (class "Default")
      (node (ref "T7") (pin "2") (pinfunction "C_2") (pintype "passive"))
      (node (ref "T8") (pin "4") (pinfunction "E_4") (pintype "passive"))
    )
    (net (code "48") (name "Net-(T10-C-Pad1)") (class "Default")
      (node (ref "T10") (pin "1") (pinfunction "C_1") (pintype "passive"))
      (node (ref "T9") (pin "3") (pinfunction "E_3") (pintype "passive"))
    )
    (net (code "49") (name "Net-(T10-C-Pad2)") (class "Default")
      (node (ref "T10") (pin "2") (pinfunction "C_2") (pintype "passive"))
      (node (ref "T9") (pin "4") (pinfunction "E_4") (pintype "passive"))
    )
    (net (code "50") (name "Net-(T14-D)") (class "Default")
      (node (ref "R125") (pin "1") (pinfunction "1_1") (pintype "passive"))
      (node (ref "R126") (pin "2") (pinfunction "2_2") (pintype "passive"))
      (node (ref "T14") (pin "3") (pinfunction "D_3") (pintype "passive"))
    )
    (net (code "51") (name "Net-(T14-G)") (class "Default")
      (node (ref "R151") (pin "2") (pinfunction "2_2") (pintype "passive"))
      (node (ref "T14") (pin "1") (pinfunction "G_1") (pintype "passive"))
    )
    (net (code "52") (name "Net-(T14-S)") (class "Default")
      (node (ref "R128") (pin "2") (pinfunction "2_2") (pintype "passive"))
      (node (ref "R152") (pin "2") (pinfunction "2_2") (pintype "passive"))
      (node (ref "T14") (pin "2") (pinfunction "S_2") (pintype "passive"))
    )
    (net (code "53") (name "Net-(T15-D)") (class "Default")
      (node (ref "R155") (pin "1") (pinfunction "1_1") (pintype "passive"))
      (node (ref "T15") (pin "3") (pinfunction "D_3") (pintype "passive"))
    )
    (net (code "54") (name "Net-(T15-G)") (class "Default")
      (node (ref "R157") (pin "2") (pinfunction "2_2") (pintype "passive"))
      (node (ref "T15") (pin "1") (pinfunction "G_1") (pintype "passive"))
    )
    (net (code "55") (name "Net-(T15-S)") (class "Default")
      (node (ref "R146") (pin "2") (pinfunction "2_2") (pintype "passive"))
      (node (ref "R147") (pin "2") (pinfunction "2_2") (pintype "passive"))
      (node (ref "T15") (pin "2") (pinfunction "S_2") (pintype "passive"))
    )
    (net (code "56") (name "P3V3s") (class "Default")
      (node (ref "C125") (pin "2") (pinfunction "2_2") (pintype "passive"))
      (node (ref "IC26") (pin "5") (pinfunction "V+_5") (pintype "power_in"))
    )
  )
)
